# mach_nguyenli.net
KiCad netlist of a schematic drawn in Altium Designer
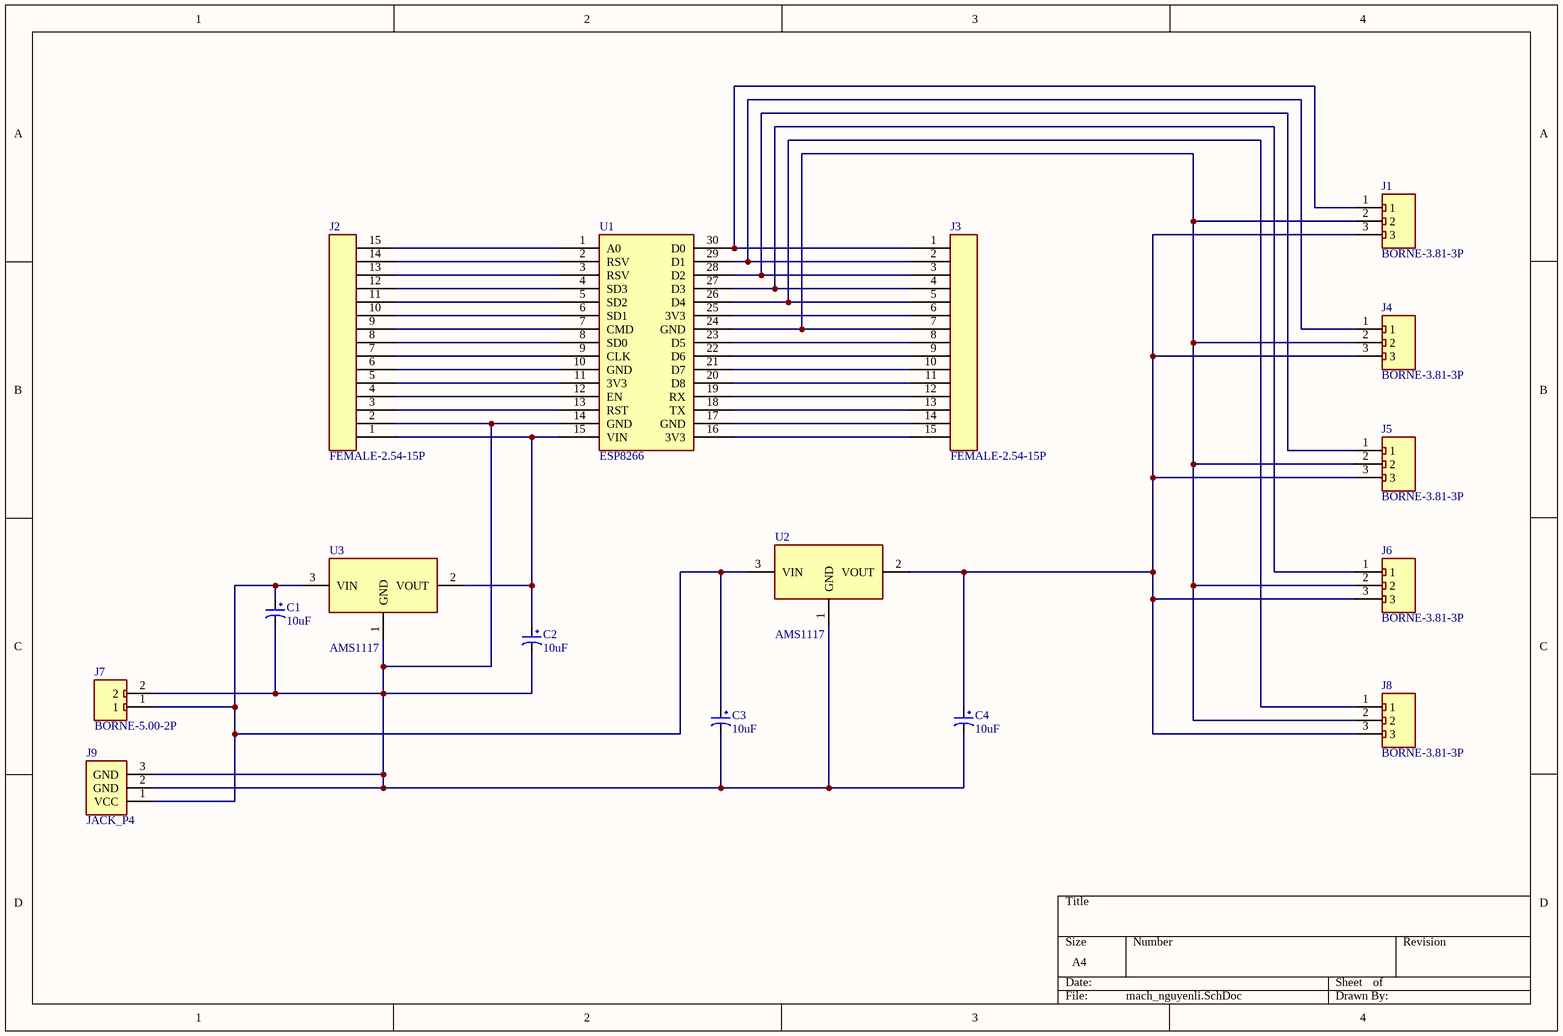
[diagram p0: mach_nguyenli.SchDoc]

(export (version "E")
  (design (tool "Eeschema 10.0.6"))
  (components
    (comp (ref "C1")
      (value "10uF")
      (footprint "CP1/2")
      (description "Cap P  0,1uF < 22uF , 16 - 50V")
      (libsource (lib "syhaunguyen") (part "CP1"))
    )
    (comp (ref "C2")
      (value "10uF")
      (footprint "CP1/2")
      (description "Cap P  0,1uF < 22uF , 16 - 50V")
      (libsource (lib "syhaunguyen") (part "CP1"))
    )
    (comp (ref "C3")
      (value "10uF")
      (footprint "CP1/2")
      (description "Cap P  0,1uF < 22uF , 16 - 50V")
      (libsource (lib "syhaunguyen") (part "CP1"))
    )
    (comp (ref "C4")
      (value "10uF")
      (footprint "CP1/2")
      (description "Cap P  0,1uF < 22uF , 16 - 50V")
      (libsource (lib "syhaunguyen") (part "CP1"))
    )
    (comp (ref "J1")
      (value "BORNE-3.81-3P")
      (footprint "BORNE-3.81-3P")
      (description "Borne 3 Vias, Pitch 3.81mm.")
      (libsource (lib "Connectors") (part "BORNE-3.81-3P"))
    )
    (comp (ref "J2")
      (value "FEMALE-2.54-15P")
      (footprint "FEMALE-2.54-15P")
      (description "Female Header Connector 2.54mm 15 Pins.")
      (libsource (lib "") (part "FEMALE-2.54-15P_1"))
    )
    (comp (ref "J3")
      (value "FEMALE-2.54-15P")
      (footprint "FEMALE-2.54-15P")
      (description "Female Header Connector 2.54mm 15 Pins.")
      (libsource (lib "Connectors") (part "FEMALE-2.54-15P"))
    )
    (comp (ref "J4")
      (value "BORNE-3.81-3P")
      (footprint "BORNE-3.81-3P")
      (description "Borne 3 Vias, Pitch 3.81mm.")
      (libsource (lib "Connectors") (part "BORNE-3.81-3P"))
    )
    (comp (ref "J5")
      (value "BORNE-3.81-3P")
      (footprint "BORNE-3.81-3P")
      (description "Borne 3 Vias, Pitch 3.81mm.")
      (libsource (lib "Connectors") (part "BORNE-3.81-3P"))
    )
    (comp (ref "J6")
      (value "BORNE-3.81-3P")
      (footprint "BORNE-3.81-3P")
      (description "Borne 3 Vias, Pitch 3.81mm.")
      (libsource (lib "Connectors") (part "BORNE-3.81-3P"))
    )
    (comp (ref "J7")
      (value "BORNE-5.00-2P")
      (footprint "BORNE-5.00-2P")
      (description "Borne 2 Vias, Pitch 5mm.")
      (libsource (lib "Connectors") (part "BORNE-5.00-2P"))
    )
    (comp (ref "J8")
      (value "BORNE-3.81-3P")
      (footprint "BORNE-3.81-3P")
      (description "Borne 3 Vias, Pitch 3.81mm.")
      (libsource (lib "Connectors") (part "BORNE-3.81-3P"))
    )
    (comp (ref "J9")
      (value "JACK_P4")
      (footprint "JACK_P4")
      (description "9V Battery Connector Jack P4.")
      (libsource (lib "Connectors") (part "JACK_P4"))
    )
    (comp (ref "U1")
      (value "ESP8266")
      (footprint "ESP8266")
      (description "Microcontoller Board 30 Pins Wifi 2.4GHz BLE 4.2 ESP-12F")
      (libsource (lib "Espressif Microcontrollers") (part "ESP8266"))
    )
    (comp (ref "U2")
      (value "AMS1117")
      (footprint "AMS1117")
      (description "IC REG LINEAR 1A SOT-89-3L")
      (libsource (lib "Voltage Regulators") (part "AMS1117"))
    )
    (comp (ref "U3")
      (value "AMS1117")
      (footprint "AMS1117")
      (description "IC REG LINEAR 1A SOT-89-3L")
      (libsource (lib "Voltage Regulators") (part "AMS1117"))
    )
  )
  (nets
    (net (code "1") (name "Net-(J1-Pad2)") (class "Default")
      (node (ref "J1") (pin "2") (pinfunction "2_2") (pintype "passive"))
      (node (ref "J3") (pin "7") (pintype "passive"))
      (node (ref "J4") (pin "2") (pinfunction "2_2") (pintype "passive"))
      (node (ref "J5") (pin "2") (pinfunction "2_2") (pintype "passive"))
      (node (ref "J6") (pin "2") (pinfunction "2_2") (pintype "passive"))
      (node (ref "J8") (pin "2") (pinfunction "2_2") (pintype "passive"))
      (node (ref "U1") (pin "24") (pinfunction "GND_24") (pintype "passive"))
    )
    (net (code "2") (name "Net-(J2-Pad5)") (class "Default")
      (node (ref "J2") (pin "5") (pintype "passive"))
      (node (ref "U1") (pin "11") (pinfunction "3V3_11") (pintype "passive"))
    )
    (net (code "3") (name "Net-(J2-Pad6)") (class "Default")
      (node (ref "J2") (pin "6") (pintype "passive"))
      (node (ref "U1") (pin "10") (pinfunction "GND_10") (pintype "passive"))
    )
    (net (code "4") (name "Net-(J2-Pad13)") (class "Default")
      (node (ref "J2") (pin "13") (pintype "passive"))
      (node (ref "U1") (pin "3") (pinfunction "RSV_3") (pintype "passive"))
    )
    (net (code "5") (name "Net-(J2-Pad14)") (class "Default")
      (node (ref "J2") (pin "14") (pintype "passive"))
      (node (ref "U1") (pin "2") (pinfunction "RSV_2") (pintype "passive"))
    )
    (net (code "6") (name "Net-(J3-Pad6)") (class "Default")
      (node (ref "J3") (pin "6") (pintype "passive"))
      (node (ref "U1") (pin "25") (pinfunction "3V3_25") (pintype "passive"))
    )
    (net (code "7") (name "Net-(J3-Pad14)") (class "Default")
      (node (ref "J3") (pin "14") (pintype "passive"))
      (node (ref "U1") (pin "17") (pinfunction "GND_17") (pintype "passive"))
    )
    (net (code "8") (name "Net-(J3-Pad15)") (class "Default")
      (node (ref "J3") (pin "15") (pintype "passive"))
      (node (ref "U1") (pin "16") (pinfunction "3V3_16") (pintype "passive"))
    )
    (net (code "9") (name "Net-(J9-VCC)") (class "Default")
      (node (ref "C1") (pin "1") (pinfunction "1_1") (pintype "passive"))
      (node (ref "C3") (pin "1") (pinfunction "1_1") (pintype "passive"))
      (node (ref "J7") (pin "1") (pinfunction "1_1") (pintype "passive"))
      (node (ref "J9") (pin "1") (pinfunction "VCC_1") (pintype "passive"))
      (node (ref "U2") (pin "3") (pinfunction "VIN_3") (pintype "passive"))
      (node (ref "U3") (pin "3") (pinfunction "VIN_3") (pintype "passive"))
    )
    (net (code "10") (name "Net-(U1-A0)") (class "Default")
      (node (ref "J2") (pin "15") (pintype "passive"))
      (node (ref "U1") (pin "1") (pinfunction "A0_1") (pintype "passive"))
    )
    (net (code "11") (name "Net-(U1-CLK)") (class "Default")
      (node (ref "J2") (pin "7") (pintype "passive"))
      (node (ref "U1") (pin "9") (pinfunction "CLK_9") (pintype "passive"))
    )
    (net (code "12") (name "Net-(U1-CMD)") (class "Default")
      (node (ref "J2") (pin "9") (pintype "passive"))
      (node (ref "U1") (pin "7") (pinfunction "CMD_7") (pintype "passive"))
    )
    (net (code "13") (name "Net-(U1-D0)") (class "Default")
      (node (ref "J1") (pin "1") (pinfunction "1_1") (pintype "passive"))
      (node (ref "J3") (pin "1") (pintype "passive"))
      (node (ref "U1") (pin "30") (pinfunction "D0_30") (pintype "passive"))
    )
    (net (code "14") (name "Net-(U1-D1)") (class "Default")
      (node (ref "J3") (pin "2") (pintype "passive"))
      (node (ref "J4") (pin "1") (pinfunction "1_1") (pintype "passive"))
      (node (ref "U1") (pin "29") (pinfunction "D1_29") (pintype "passive"))
    )
    (net (code "15") (name "Net-(U1-D2)") (class "Default")
      (node (ref "J3") (pin "3") (pintype "passive"))
      (node (ref "J5") (pin "1") (pinfunction "1_1") (pintype "passive"))
      (node (ref "U1") (pin "28") (pinfunction "D2_28") (pintype "passive"))
    )
    (net (code "16") (name "Net-(U1-D3)") (class "Default")
      (node (ref "J3") (pin "4") (pintype "passive"))
      (node (ref "J6") (pin "1") (pinfunction "1_1") (pintype "passive"))
      (node (ref "U1") (pin "27") (pinfunction "D3_27") (pintype "passive"))
    )
    (net (code "17") (name "Net-(U1-D4)") (class "Default")
      (node (ref "J3") (pin "5") (pintype "passive"))
      (node (ref "J8") (pin "1") (pinfunction "1_1") (pintype "passive"))
      (node (ref "U1") (pin "26") (pinfunction "D4_26") (pintype "passive"))
    )
    (net (code "18") (name "Net-(U1-D5)") (class "Default")
      (node (ref "J3") (pin "8") (pintype "passive"))
      (node (ref "U1") (pin "23") (pinfunction "D5_23") (pintype "passive"))
    )
    (net (code "19") (name "Net-(U1-D6)") (class "Default")
      (node (ref "J3") (pin "9") (pintype "passive"))
      (node (ref "U1") (pin "22") (pinfunction "D6_22") (pintype "passive"))
    )
    (net (code "20") (name "Net-(U1-D7)") (class "Default")
      (node (ref "J3") (pin "10") (pintype "passive"))
      (node (ref "U1") (pin "21") (pinfunction "D7_21") (pintype "passive"))
    )
    (net (code "21") (name "Net-(U1-D8)") (class "Default")
      (node (ref "J3") (pin "11") (pintype "passive"))
      (node (ref "U1") (pin "20") (pinfunction "D8_20") (pintype "passive"))
    )
    (net (code "22") (name "Net-(U1-EN)") (class "Default")
      (node (ref "J2") (pin "4") (pintype "passive"))
      (node (ref "U1") (pin "12") (pinfunction "EN_12") (pintype "passive"))
    )
    (net (code "23") (name "Net-(U1-RST)") (class "Default")
      (node (ref "J2") (pin "3") (pintype "passive"))
      (node (ref "U1") (pin "13") (pinfunction "RST_13") (pintype "passive"))
    )
    (net (code "24") (name "Net-(U1-RX)") (class "Default")
      (node (ref "J3") (pin "12") (pintype "passive"))
      (node (ref "U1") (pin "19") (pinfunction "RX_19") (pintype "passive"))
    )
    (net (code "25") (name "Net-(U1-SD0)") (class "Default")
      (node (ref "J2") (pin "8") (pintype "passive"))
      (node (ref "U1") (pin "8") (pinfunction "SD0_8") (pintype "passive"))
    )
    (net (code "26") (name "Net-(U1-SD1)") (class "Default")
      (node (ref "J2") (pin "10") (pintype "passive"))
      (node (ref "U1") (pin "6") (pinfunction "SD1_6") (pintype "passive"))
    )
    (net (code "27") (name "Net-(U1-SD2)") (class "Default")
      (node (ref "J2") (pin "11") (pintype "passive"))
      (node (ref "U1") (pin "5") (pinfunction "SD2_5") (pintype "passive"))
    )
    (net (code "28") (name "Net-(U1-SD3)") (class "Default")
      (node (ref "J2") (pin "12") (pintype "passive"))
      (node (ref "U1") (pin "4") (pinfunction "SD3_4") (pintype "passive"))
    )
    (net (code "29") (name "Net-(U1-TX)") (class "Default")
      (node (ref "J3") (pin "13") (pintype "passive"))
      (node (ref "U1") (pin "18") (pinfunction "TX_18") (pintype "passive"))
    )
    (net (code "30") (name "Net-(U1-VIN)") (class "Default")
      (node (ref "C2") (pin "1") (pinfunction "1_1") (pintype "passive"))
      (node (ref "J2") (pin "1") (pintype "passive"))
      (node (ref "U1") (pin "15") (pinfunction "VIN_15") (pintype "passive"))
      (node (ref "U3") (pin "2") (pinfunction "VOUT_2") (pintype "passive"))
    )
    (net (code "31") (name "Net-(U2-GND)") (class "Default")
      (node (ref "C1") (pin "2") (pinfunction "2_2") (pintype "passive"))
      (node (ref "C2") (pin "2") (pinfunction "2_2") (pintype "passive"))
      (node (ref "C3") (pin "2") (pinfunction "2_2") (pintype "passive"))
      (node (ref "C4") (pin "2") (pinfunction "2_2") (pintype "passive"))
      (node (ref "J2") (pin "2") (pintype "passive"))
      (node (ref "J7") (pin "2") (pinfunction "2_2") (pintype "passive"))
      (node (ref "J9") (pin "2") (pinfunction "GND_2") (pintype "passive"))
      (node (ref "J9") (pin "3") (pinfunction "GND_3") (pintype "passive"))
      (node (ref "U1") (pin "14") (pinfunction "GND_14") (pintype "passive"))
      (node (ref "U2") (pin "1") (pinfunction "GND_1") (pintype "passive"))
      (node (ref "U3") (pin "1") (pinfunction "GND_1") (pintype "passive"))
    )
    (net (code "32") (name "Net-(U2-VOUT)") (class "Default")
      (node (ref "C4") (pin "1") (pinfunction "1_1") (pintype "passive"))
      (node (ref "J1") (pin "3") (pinfunction "3_3") (pintype "passive"))
      (node (ref "J4") (pin "3") (pinfunction "3_3") (pintype "passive"))
      (node (ref "J5") (pin "3") (pinfunction "3_3") (pintype "passive"))
      (node (ref "J6") (pin "3") (pinfunction "3_3") (pintype "passive"))
      (node (ref "J8") (pin "3") (pinfunction "3_3") (pintype "passive"))
      (node (ref "U2") (pin "2") (pinfunction "VOUT_2") (pintype "passive"))
    )
  )
)
